# Humidifier.net
KiCad netlist of a schematic drawn in Altium Designer
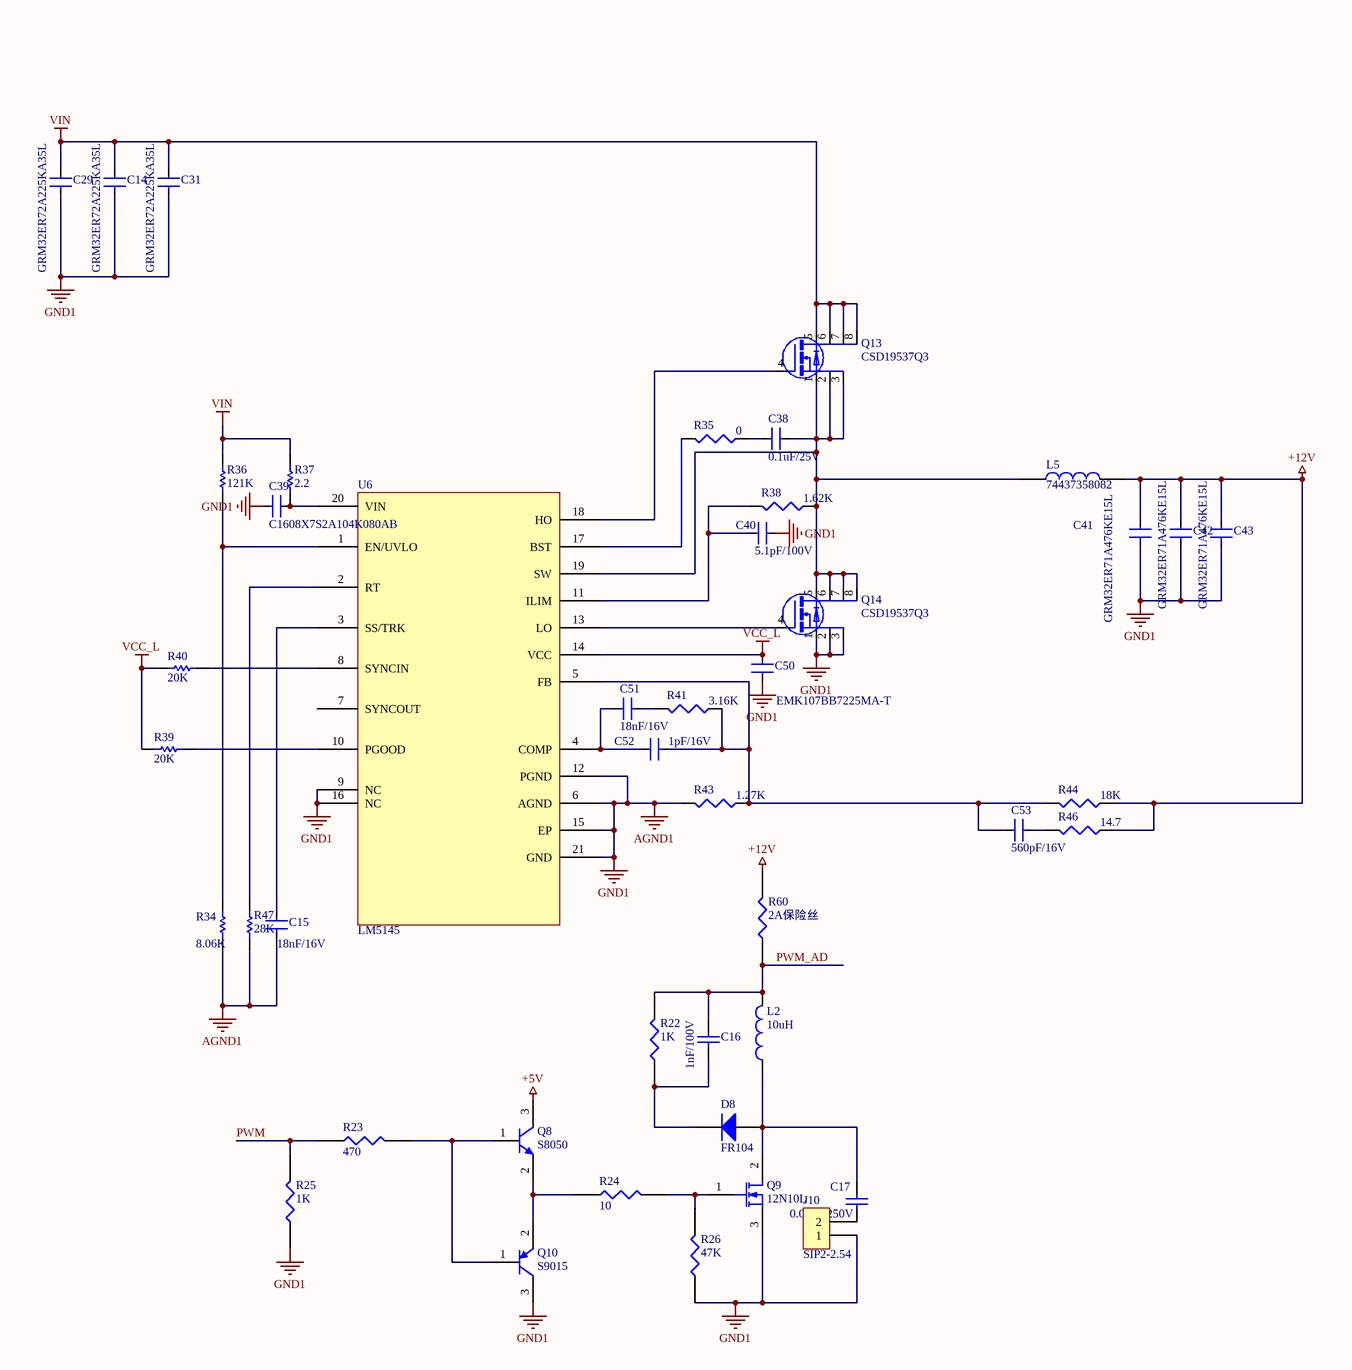
[diagram p0: Humidifier.SchDoc]

(export (version "E")
  (design (tool "Eeschema 10.0.6"))
  (components
    (comp (ref "C14")
      (value "GRM32ER72A225KA35L")
      (footprint "1210C")
      (description "CCX85-103")
      (libsource (lib "无极性电容") (part "0.01UF"))
    )
    (comp (ref "C15")
      (value "18nF/16V")
      (footprint "0603C")
      (description "CCX85-103")
      (libsource (lib "无极性电容") (part "0.01UF"))
    )
    (comp (ref "C16")
      (value "1nF/100V")
      (footprint "CAP_5MM")
      (description "Capacitor")
      (fields (field (name "PUBLISHER") "Altium Limited"))
      (libsource (lib "Miscellaneous Devices") (part "Cap"))
    )
    (comp (ref "C17")
      (value "0.047F/250V")
      (footprint "CAP_5MM")
      (description "Capacitor")
      (fields (field (name "PUBLISHER") "Altium Limited"))
      (libsource (lib "Miscellaneous Devices") (part "Cap"))
    )
    (comp (ref "C29")
      (value "GRM32ER72A225KA35L")
      (footprint "1210C")
      (description "CCX85-103")
      (libsource (lib "无极性电容") (part "0.01UF"))
    )
    (comp (ref "C31")
      (value "GRM32ER72A225KA35L")
      (footprint "1210C")
      (description "CCX85-103")
      (libsource (lib "无极性电容") (part "0.01UF"))
    )
    (comp (ref "C38")
      (value "0.1uF/25V")
      (footprint "0603C")
      (description "CCX85-103")
      (libsource (lib "无极性电容") (part "0.01UF"))
    )
    (comp (ref "C39")
      (value "C1608X7S2A104K080AB")
      (footprint "0603C")
      (description "CCX85-103")
      (libsource (lib "无极性电容") (part "0.01UF"))
    )
    (comp (ref "C40")
      (value "5.1pF/100V")
      (footprint "0603C")
      (description "CCX85-103")
      (libsource (lib "无极性电容") (part "0.01UF"))
    )
    (comp (ref "C41")
      (value "GRM32ER71A476KE15L")
      (footprint "1210C")
      (description "CCX85-103")
      (libsource (lib "无极性电容") (part "0.01UF"))
    )
    (comp (ref "C42")
      (value "GRM32ER71A476KE15L")
      (footprint "1210C")
      (description "CCX85-103")
      (libsource (lib "无极性电容") (part "0.01UF"))
    )
    (comp (ref "C43")
      (value "GRM32ER71A476KE15L")
      (footprint "1210C")
      (description "CCX85-103")
      (libsource (lib "无极性电容") (part "0.01UF"))
    )
    (comp (ref "C50")
      (value "EMK107BB7225MA-T")
      (footprint "0603C")
      (description "CCX85-103")
      (libsource (lib "无极性电容") (part "0.01UF"))
    )
    (comp (ref "C51")
      (value "18nF/16V")
      (footprint "0603C")
      (description "CCX85-103")
      (libsource (lib "无极性电容") (part "0.01UF"))
    )
    (comp (ref "C52")
      (value "1pF/16V")
      (footprint "0603C")
      (description "CCX85-103")
      (libsource (lib "无极性电容") (part "0.01UF"))
    )
    (comp (ref "C53")
      (value "560pF/16V")
      (footprint "0603C")
      (description "CCX85-103")
      (libsource (lib "无极性电容") (part "0.01UF"))
    )
    (comp (ref "D8")
      (value "FR104")
      (footprint "SMA")
      (description "Default Diode")
      (fields (field (name "PUBLISHER") "Altium Limited"))
      (libsource (lib "SM") (part "Diode_2"))
    )
    (comp (ref "J10")
      (value "SIP2-2.54")
      (footprint "SIP-2L")
      (description "CN-SIP2-2.54")
      (libsource (lib "接插件") (part "SIP2-2.54"))
    )
    (comp (ref "L2")
      (value "10uH")
      (footprint "6*8")
      (description "Inductor")
      (fields (field (name "PUBLISHER") "Altium Limited"))
      (libsource (lib "Miscellaneous Devices") (part "Inductor"))
    )
    (comp (ref "L5") (value "74437358082") (footprint "SRP1270-2R2M") (libsource (lib "*") (part "INDUCTOR")))
    (comp (ref "Q8")
      (value "S8050")
      (footprint "SOT23-3")
      (description "NPN Bipolar Transistor")
      (fields (field (name "PUBLISHER") "Altium Limited"))
      (libsource (lib "Miscellaneous Devices") (part "NPN"))
    )
    (comp (ref "Q9")
      (value "12N10L")
      (footprint "TO230P973X238-3N")
      (description "N-Channel MOSFET")
      (fields (field (name "PUBLISHER") "Altium Limited"))
      (libsource (lib "Miscellaneous Devices") (part "MOSFET-N"))
    )
    (comp (ref "Q10")
      (value "S9015")
      (footprint "SOT23-3")
      (description "PNP Bipolar Transistor")
      (fields (field (name "PUBLISHER") "Altium Limited"))
      (libsource (lib "Miscellaneous Devices") (part "PNP"))
    )
    (comp (ref "Q13")
      (value "CSD19537Q3")
      (footprint "PowerPAK SO-8")
      (description "Si4004DY")
      (libsource (lib "Schlib_20110825") (part "Si4004DY"))
    )
    (comp (ref "Q14")
      (value "CSD19537Q3")
      (footprint "PowerPAK SO-8")
      (description "Si4004DY")
      (libsource (lib "Schlib_20110825") (part "Si4004DY"))
    )
    (comp (ref "R22") (value "1K") (footprint "0805R") (libsource (lib "其他电阻") (part "RES1")))
    (comp (ref "R23") (value "470") (footprint "0805R") (libsource (lib "其他电阻") (part "RES1")))
    (comp (ref "R24") (value "10") (footprint "0805R") (libsource (lib "其他电阻") (part "RES1")))
    (comp (ref "R25") (value "1K") (footprint "0805R") (libsource (lib "其他电阻") (part "RES1")))
    (comp (ref "R26") (value "47K") (footprint "0805R") (libsource (lib "其他电阻") (part "RES1")))
    (comp (ref "R34")
      (value "8.06K")
      (footprint "0603R")
      (description "Semiconductor Resistor")
      (fields (field (name "PUBLISHER") "Altium Limited"))
      (libsource (lib "Miscellaneous Devices") (part "Res Semi"))
    )
    (comp (ref "R35")
      (value "0")
      (footprint "0603R")
      (description "Resistor")
      (fields (field (name "PUBLISHER") "Altium Limited"))
      (libsource (lib "SM") (part "Res3"))
    )
    (comp (ref "R36")
      (value "121K")
      (footprint "0805R")
      (description "Semiconductor Resistor")
      (fields (field (name "PUBLISHER") "Altium Limited"))
      (libsource (lib "Miscellaneous Devices") (part "Res Semi"))
    )
    (comp (ref "R37")
      (value "2.2")
      (footprint "0603R")
      (description "Semiconductor Resistor")
      (fields (field (name "PUBLISHER") "Altium Limited"))
      (libsource (lib "Miscellaneous Devices") (part "Res Semi"))
    )
    (comp (ref "R38")
      (value "1.62K")
      (footprint "0603R")
      (description "Resistor")
      (fields (field (name "PUBLISHER") "Altium Limited"))
      (libsource (lib "SM") (part "Res3"))
    )
    (comp (ref "R39")
      (value "20K")
      (footprint "0603R")
      (description "Semiconductor Resistor")
      (fields (field (name "PUBLISHER") "Altium Limited"))
      (libsource (lib "Miscellaneous Devices") (part "Res Semi"))
    )
    (comp (ref "R40")
      (value "20K")
      (footprint "0603R")
      (description "Semiconductor Resistor")
      (fields (field (name "PUBLISHER") "Altium Limited"))
      (libsource (lib "Miscellaneous Devices") (part "Res Semi"))
    )
    (comp (ref "R41")
      (value "3.16K")
      (footprint "0603R")
      (description "Resistor")
      (fields (field (name "PUBLISHER") "Altium Limited"))
      (libsource (lib "SM") (part "Res3"))
    )
    (comp (ref "R43")
      (value "1.27K")
      (footprint "0603R")
      (description "Resistor")
      (fields (field (name "PUBLISHER") "Altium Limited"))
      (libsource (lib "SM") (part "Res3"))
    )
    (comp (ref "R44")
      (value "18K")
      (footprint "0603R")
      (description "Resistor")
      (fields (field (name "PUBLISHER") "Altium Limited"))
      (libsource (lib "SM") (part "Res3"))
    )
    (comp (ref "R46")
      (value "14.7")
      (footprint "0603R")
      (description "Resistor")
      (fields (field (name "PUBLISHER") "Altium Limited"))
      (libsource (lib "SM") (part "Res3"))
    )
    (comp (ref "R47")
      (value "28K")
      (footprint "0603R")
      (description "Semiconductor Resistor")
      (fields (field (name "PUBLISHER") "Altium Limited"))
      (libsource (lib "Miscellaneous Devices") (part "Res Semi"))
    )
    (comp (ref "R60") (value "2A保险丝") (footprint "0805R") (libsource (lib "其他电阻") (part "RES1")))
    (comp (ref "U6")
      (value "LM5145")
      (footprint "QFN050P600-8N")
      (libsource (lib "Schlib_20110825") (part "LM5145"))
    )
  )
  (nets
    (net (code "1") (name "+5V") (class "Default")
      (node (ref "Q8") (pin "3") (pinfunction "C_3") (pintype "passive"))
    )
    (net (code "2") (name "+12V") (class "Default")
      (node (ref "C41") (pin "1") (pinfunction "1_1") (pintype "passive"))
      (node (ref "C42") (pin "1") (pinfunction "1_1") (pintype "passive"))
      (node (ref "C43") (pin "1") (pinfunction "1_1") (pintype "passive"))
      (node (ref "L5") (pin "2") (pinfunction "2_2") (pintype "passive"))
      (node (ref "R44") (pin "1") (pinfunction "1_1") (pintype "passive"))
      (node (ref "R46") (pin "1") (pinfunction "1_1") (pintype "passive"))
      (node (ref "R60") (pin "2") (pinfunction "2_2") (pintype "passive"))
    )
    (net (code "3") (name "/PWM") (class "Default")
      (node (ref "R23") (pin "1") (pinfunction "1_1") (pintype "passive"))
      (node (ref "R25") (pin "2") (pinfunction "2_2") (pintype "passive"))
    )
    (net (code "4") (name "/PWM_AD") (class "Default")
      (node (ref "C16") (pin "2") (pinfunction "2_2") (pintype "passive"))
      (node (ref "L2") (pin "2") (pinfunction "2_2") (pintype "passive"))
      (node (ref "R22") (pin "2") (pinfunction "2_2") (pintype "passive"))
      (node (ref "R60") (pin "1") (pinfunction "1_1") (pintype "passive"))
    )
    (net (code "5") (name "AGND1") (class "Default")
      (node (ref "C14") (pin "2") (pinfunction "2_2") (pintype "passive"))
      (node (ref "C15") (pin "2") (pinfunction "2_2") (pintype "passive"))
      (node (ref "C29") (pin "2") (pinfunction "2_2") (pintype "passive"))
      (node (ref "C31") (pin "2") (pinfunction "2_2") (pintype "passive"))
      (node (ref "C39") (pin "1") (pinfunction "1_1") (pintype "passive"))
      (node (ref "C40") (pin "1") (pinfunction "1_1") (pintype "passive"))
      (node (ref "C41") (pin "2") (pinfunction "2_2") (pintype "passive"))
      (node (ref "C42") (pin "2") (pinfunction "2_2") (pintype "passive"))
      (node (ref "C43") (pin "2") (pinfunction "2_2") (pintype "passive"))
      (node (ref "C50") (pin "2") (pinfunction "2_2") (pintype "passive"))
      (node (ref "J10") (pin "1") (pinfunction "1_1") (pintype "passive"))
      (node (ref "Q10") (pin "3") (pinfunction "C_3") (pintype "passive"))
      (node (ref "Q14") (pin "1") (pinfunction "S_1") (pintype "passive"))
      (node (ref "Q14") (pin "2") (pinfunction "S_2") (pintype "passive"))
      (node (ref "Q14") (pin "3") (pinfunction "S_3") (pintype "passive"))
      (node (ref "Q9") (pin "3") (pinfunction "S_3") (pintype "passive"))
      (node (ref "R25") (pin "1") (pinfunction "1_1") (pintype "passive"))
      (node (ref "R26") (pin "1") (pinfunction "1_1") (pintype "passive"))
      (node (ref "R34") (pin "1") (pinfunction "1_1") (pintype "passive"))
      (node (ref "R43") (pin "2") (pinfunction "2_2") (pintype "passive"))
      (node (ref "R47") (pin "1") (pinfunction "1_1") (pintype "passive"))
      (node (ref "U6") (pin "12") (pinfunction "PGND_12") (pintype "passive"))
      (node (ref "U6") (pin "15") (pinfunction "EP_15") (pintype "passive"))
      (node (ref "U6") (pin "16") (pinfunction "NC_16") (pintype "passive"))
      (node (ref "U6") (pin "21") (pinfunction "GND_21") (pintype "passive"))
      (node (ref "U6") (pin "6") (pinfunction "AGND_6") (pintype "passive"))
      (node (ref "U6") (pin "9") (pinfunction "NC_9") (pintype "passive"))
    )
    (net (code "6") (name "Net-(C17-Pad1)") (class "Default")
      (node (ref "C17") (pin "1") (pinfunction "1_1") (pintype "passive"))
      (node (ref "J10") (pin "2") (pinfunction "2_2") (pintype "passive"))
    )
    (net (code "7") (name "Net-(C38-Pad1)") (class "Default")
      (node (ref "C38") (pin "1") (pinfunction "1_1") (pintype "passive"))
      (node (ref "R35") (pin "1") (pinfunction "1_1") (pintype "passive"))
    )
    (net (code "8") (name "Net-(C51-Pad2)") (class "Default")
      (node (ref "C51") (pin "2") (pinfunction "2_2") (pintype "passive"))
      (node (ref "R41") (pin "2") (pinfunction "2_2") (pintype "passive"))
    )
    (net (code "9") (name "Net-(C53-Pad2)") (class "Default")
      (node (ref "C53") (pin "2") (pinfunction "2_2") (pintype "passive"))
      (node (ref "R46") (pin "2") (pinfunction "2_2") (pintype "passive"))
    )
    (net (code "10") (name "Net-(D8-A)") (class "Default")
      (node (ref "C17") (pin "2") (pinfunction "2_2") (pintype "passive"))
      (node (ref "D8") (pin "1") (pinfunction "A_1") (pintype "passive"))
      (node (ref "L2") (pin "1") (pinfunction "1_1") (pintype "passive"))
      (node (ref "Q9") (pin "2") (pinfunction "D_2") (pintype "passive"))
    )
    (net (code "11") (name "Net-(D8-K)") (class "Default")
      (node (ref "C16") (pin "1") (pinfunction "1_1") (pintype "passive"))
      (node (ref "D8") (pin "2") (pinfunction "K_2") (pintype "passive"))
      (node (ref "R22") (pin "1") (pinfunction "1_1") (pintype "passive"))
    )
    (net (code "12") (name "Net-(Q9-G)") (class "Default")
      (node (ref "Q9") (pin "1") (pinfunction "G_1") (pintype "passive"))
      (node (ref "R24") (pin "2") (pinfunction "2_2") (pintype "passive"))
      (node (ref "R26") (pin "2") (pinfunction "2_2") (pintype "passive"))
    )
    (net (code "13") (name "Net-(Q10-B)") (class "Default")
      (node (ref "Q10") (pin "1") (pinfunction "B_1") (pintype "passive"))
      (node (ref "Q8") (pin "1") (pinfunction "B_1") (pintype "passive"))
      (node (ref "R23") (pin "2") (pinfunction "2_2") (pintype "passive"))
    )
    (net (code "14") (name "Net-(Q10-E)") (class "Default")
      (node (ref "Q10") (pin "2") (pinfunction "E_2") (pintype "passive"))
      (node (ref "Q8") (pin "2") (pinfunction "E_2") (pintype "passive"))
      (node (ref "R24") (pin "1") (pinfunction "1_1") (pintype "passive"))
    )
    (net (code "15") (name "Net-(Q13-G)") (class "Default")
      (node (ref "Q13") (pin "4") (pinfunction "G_4") (pintype "passive"))
      (node (ref "U6") (pin "18") (pinfunction "HO_18") (pintype "passive"))
    )
    (net (code "16") (name "Net-(Q14-G)") (class "Default")
      (node (ref "Q14") (pin "4") (pinfunction "G_4") (pintype "passive"))
      (node (ref "U6") (pin "13") (pinfunction "LO_13") (pintype "passive"))
    )
    (net (code "17") (name "Net-(U6-BST)") (class "Default")
      (node (ref "R35") (pin "2") (pinfunction "2_2") (pintype "passive"))
      (node (ref "U6") (pin "17") (pinfunction "BST_17") (pintype "passive"))
    )
    (net (code "18") (name "Net-(U6-COMP)") (class "Default")
      (node (ref "C51") (pin "1") (pinfunction "1_1") (pintype "passive"))
      (node (ref "C52") (pin "1") (pinfunction "1_1") (pintype "passive"))
      (node (ref "U6") (pin "4") (pinfunction "COMP_4") (pintype "passive"))
    )
    (net (code "19") (name "Net-(U6-EN{slash}UVLO)") (class "Default")
      (node (ref "R34") (pin "2") (pinfunction "2_2") (pintype "passive"))
      (node (ref "R36") (pin "1") (pinfunction "1_1") (pintype "passive"))
      (node (ref "U6") (pin "1") (pinfunction "EN/UVLO_1") (pintype "passive"))
    )
    (net (code "20") (name "Net-(U6-FB)") (class "Default")
      (node (ref "C52") (pin "2") (pinfunction "2_2") (pintype "passive"))
      (node (ref "C53") (pin "1") (pinfunction "1_1") (pintype "passive"))
      (node (ref "R41") (pin "1") (pinfunction "1_1") (pintype "passive"))
      (node (ref "R43") (pin "1") (pinfunction "1_1") (pintype "passive"))
      (node (ref "R44") (pin "2") (pinfunction "2_2") (pintype "passive"))
      (node (ref "U6") (pin "5") (pinfunction "FB_5") (pintype "passive"))
    )
    (net (code "21") (name "Net-(U6-ILIM)") (class "Default")
      (node (ref "C40") (pin "2") (pinfunction "2_2") (pintype "passive"))
      (node (ref "R38") (pin "2") (pinfunction "2_2") (pintype "passive"))
      (node (ref "U6") (pin "11") (pinfunction "ILIM_11") (pintype "passive"))
    )
    (net (code "22") (name "Net-(U6-PGOOD)") (class "Default")
      (node (ref "R39") (pin "1") (pinfunction "1_1") (pintype "passive"))
      (node (ref "U6") (pin "10") (pinfunction "PGOOD_10") (pintype "passive"))
    )
    (net (code "23") (name "Net-(U6-RT)") (class "Default")
      (node (ref "R47") (pin "2") (pinfunction "2_2") (pintype "passive"))
      (node (ref "U6") (pin "2") (pinfunction "RT_2") (pintype "passive"))
    )
    (net (code "24") (name "Net-(U6-SS{slash}TRK)") (class "Default")
      (node (ref "C15") (pin "1") (pinfunction "1_1") (pintype "passive"))
      (node (ref "U6") (pin "3") (pinfunction "SS/TRK_3") (pintype "passive"))
    )
    (net (code "25") (name "Net-(U6-SW)") (class "Default")
      (node (ref "C38") (pin "2") (pinfunction "2_2") (pintype "passive"))
      (node (ref "L5") (pin "1") (pinfunction "1_1") (pintype "passive"))
      (node (ref "Q13") (pin "1") (pinfunction "S_1") (pintype "passive"))
      (node (ref "Q13") (pin "2") (pinfunction "S_2") (pintype "passive"))
      (node (ref "Q13") (pin "3") (pinfunction "S_3") (pintype "passive"))
      (node (ref "Q14") (pin "5") (pinfunction "D_5") (pintype "passive"))
      (node (ref "Q14") (pin "6") (pinfunction "D_6") (pintype "passive"))
      (node (ref "Q14") (pin "7") (pinfunction "D_7") (pintype "passive"))
      (node (ref "Q14") (pin "8") (pinfunction "D_8") (pintype "passive"))
      (node (ref "R38") (pin "1") (pinfunction "1_1") (pintype "passive"))
      (node (ref "U6") (pin "19") (pinfunction "SW_19") (pintype "passive"))
    )
    (net (code "26") (name "Net-(U6-SYNCIN)") (class "Default")
      (node (ref "R40") (pin "1") (pinfunction "1_1") (pintype "passive"))
      (node (ref "U6") (pin "8") (pinfunction "SYNCIN_8") (pintype "passive"))
    )
    (net (code "27") (name "Net-(U6-VIN)") (class "Default")
      (node (ref "C39") (pin "2") (pinfunction "2_2") (pintype "passive"))
      (node (ref "R37") (pin "2") (pinfunction "2_2") (pintype "passive"))
      (node (ref "U6") (pin "20") (pinfunction "VIN_20") (pintype "passive"))
    )
    (net (code "28") (name "VCC_L") (class "Default")
      (node (ref "C50") (pin "1") (pinfunction "1_1") (pintype "passive"))
      (node (ref "R39") (pin "2") (pinfunction "2_2") (pintype "passive"))
      (node (ref "R40") (pin "2") (pinfunction "2_2") (pintype "passive"))
      (node (ref "U6") (pin "14") (pinfunction "VCC_14") (pintype "passive"))
    )
    (net (code "29") (name "VIN") (class "Default")
      (node (ref "C14") (pin "1") (pinfunction "1_1") (pintype "passive"))
      (node (ref "C29") (pin "1") (pinfunction "1_1") (pintype "passive"))
      (node (ref "C31") (pin "1") (pinfunction "1_1") (pintype "passive"))
      (node (ref "Q13") (pin "5") (pinfunction "D_5") (pintype "passive"))
      (node (ref "Q13") (pin "6") (pinfunction "D_6") (pintype "passive"))
      (node (ref "Q13") (pin "7") (pinfunction "D_7") (pintype "passive"))
      (node (ref "Q13") (pin "8") (pinfunction "D_8") (pintype "passive"))
      (node (ref "R36") (pin "2") (pinfunction "2_2") (pintype "passive"))
      (node (ref "R37") (pin "1") (pinfunction "1_1") (pintype "passive"))
    )
    (net (code "30") (name "unconnected-(U6-SYNCOUT-Pad7)") (class "Default")
      (node (ref "U6") (pin "7") (pinfunction "SYNCOUT_7") (pintype "passive"))
    )
  )
)
